# untitled.net
KiCad netlist of a schematic drawn in EAGLE
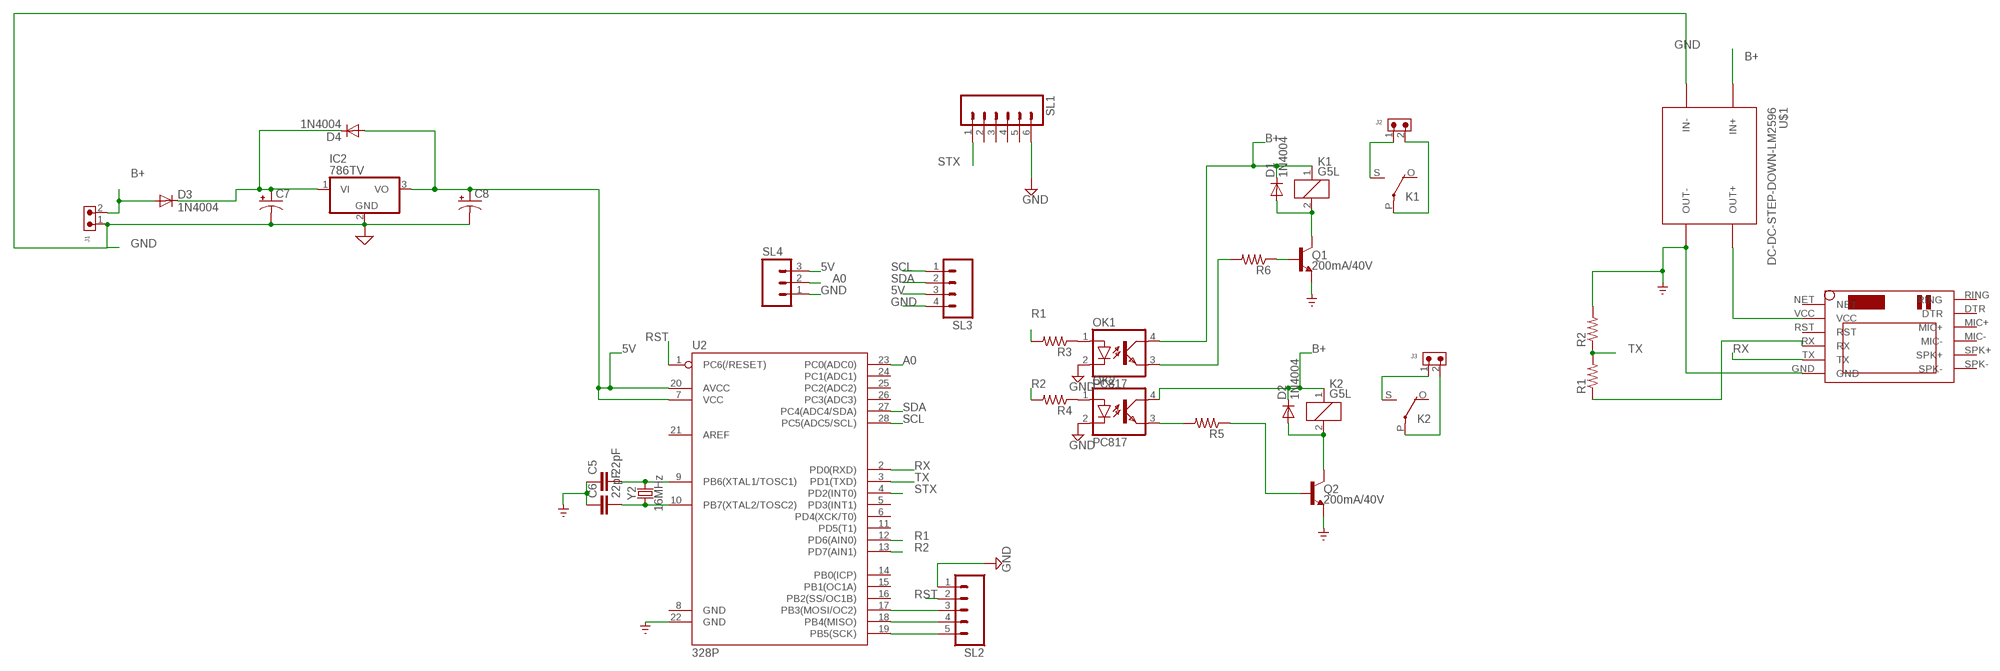
[diagram p0: schematic, sheet 1]

(export (version "E")
  (design (tool "Eeschema 10.0.6"))
  (components
    (comp (ref "C5")
      (value "22pF")
      (footprint "eagle-import:CAP-PTH-2.54")
      (libsource (lib "eagle-import") (part "22PF-PTH-2.54MM-200V-5%"))
    )
    (comp (ref "C6")
      (value "22pF")
      (footprint "eagle-import:CAP-PTH-2.54")
      (libsource (lib "eagle-import") (part "22PF-PTH-2.54MM-200V-5%"))
    )
    (comp (ref "C7")
      (value "CAPACITOR-PE5-10.5")
      (footprint "eagle-import:E5-10,5")
      (libsource (lib "eagle-import") (part "CAPACITOR-PE5-10.5"))
    )
    (comp (ref "C8")
      (value "CAPACITOR-PE5-6")
      (footprint "eagle-import:E5-6")
      (libsource (lib "eagle-import") (part "CAPACITOR-PE5-6"))
    )
    (comp (ref "D1")
      (value "1N4004")
      (footprint "eagle-import:DO41-10")
      (libsource (lib "eagle-import") (part "1N4004"))
    )
    (comp (ref "D2")
      (value "1N4004")
      (footprint "eagle-import:DO41-10")
      (libsource (lib "eagle-import") (part "1N4004"))
    )
    (comp (ref "D3")
      (value "1N4004")
      (footprint "eagle-import:DO41-10")
      (libsource (lib "eagle-import") (part "1N4004"))
    )
    (comp (ref "D4")
      (value "1N4004")
      (footprint "eagle-import:DO41-10")
      (libsource (lib "eagle-import") (part "1N4004"))
    )
    (comp (ref "IC2")
      (value "786TV")
      (footprint "eagle-import:TO220V")
      (libsource (lib "eagle-import") (part "78TV6"))
    )
    (comp (ref "J1")
      (value "691305530002")
      (footprint "eagle-import:691305530002")
      (libsource (lib "eagle-import") (part "691305530002"))
    )
    (comp (ref "J2")
      (value "691305530002")
      (footprint "eagle-import:691305530002")
      (libsource (lib "eagle-import") (part "691305530002"))
    )
    (comp (ref "J3")
      (value "691305530002")
      (footprint "eagle-import:691305530002")
      (libsource (lib "eagle-import") (part "691305530002"))
    )
    (comp (ref "K1")
      (value "G5L")
      (footprint "eagle-import:G5LE")
      (libsource (lib "eagle-import") (part "G5L"))
    )
    (comp (ref "K2")
      (value "G5L")
      (footprint "eagle-import:G5LE")
      (libsource (lib "eagle-import") (part "G5L"))
    )
    (comp (ref "OK1")
      (value "PC817")
      (footprint "eagle-import:DIL04")
      (fields (field (name "MPN") "PC817X4J000F"))
      (libsource (lib "eagle-import") (part "PC817"))
    )
    (comp (ref "OK2")
      (value "PC817")
      (footprint "eagle-import:DIL04")
      (fields (field (name "MPN") "PC817X4J000F"))
      (libsource (lib "eagle-import") (part "PC817"))
    )
    (comp (ref "Q1")
      (value "200mA/40V")
      (footprint "eagle-import:TO-92")
      (libsource (lib "eagle-import") (part "TRANS_NPN-2N3904"))
    )
    (comp (ref "Q2")
      (value "200mA/40V")
      (footprint "eagle-import:TO-92")
      (libsource (lib "eagle-import") (part "TRANS_NPN-2N3904"))
    )
    (comp (ref "R1")
      (value "R-US_0207/9")
      (footprint "eagle-import:0207_9")
      (libsource (lib "eagle-import") (part "R-US_0207/9"))
    )
    (comp (ref "R2")
      (value "R-US_0207/9")
      (footprint "eagle-import:0207_9")
      (libsource (lib "eagle-import") (part "R-US_0207/9"))
    )
    (comp (ref "R3")
      (value "R-US_0207/9")
      (footprint "eagle-import:0207_9")
      (libsource (lib "eagle-import") (part "R-US_0207/9"))
    )
    (comp (ref "R4")
      (value "R-US_0207/9")
      (footprint "eagle-import:0207_9")
      (libsource (lib "eagle-import") (part "R-US_0207/9"))
    )
    (comp (ref "R5")
      (value "R-US_0207/9")
      (footprint "eagle-import:0207_9")
      (libsource (lib "eagle-import") (part "R-US_0207/9"))
    )
    (comp (ref "R6")
      (value "R-US_0207/9")
      (footprint "eagle-import:0207_9")
      (libsource (lib "eagle-import") (part "R-US_0207/9"))
    )
    (comp (ref "SL1")
      (value "M06")
      (footprint "eagle-import:06P")
      (libsource (lib "eagle-import") (part "M06"))
    )
    (comp (ref "SL2")
      (value "M05")
      (footprint "eagle-import:05P")
      (libsource (lib "eagle-import") (part "M05"))
    )
    (comp (ref "SL3")
      (value "M04")
      (footprint "eagle-import:04P")
      (libsource (lib "eagle-import") (part "M04"))
    )
    (comp (ref "SL4")
      (value "M03")
      (footprint "eagle-import:03P")
      (libsource (lib "eagle-import") (part "M03"))
    )
    (comp (ref "U$1")
      (value "DC-DC-STEP-DOWN-LM2596")
      (footprint "eagle-import:DC-DC-STEP-DOWN-LM2596")
      (libsource (lib "eagle-import") (part "DC-DC-STEP-DOWN-LM2596"))
    )
    (comp (ref "U$2")
      (value "SIM800LMODULE")
      (footprint "eagle-import:SIM800LMODULE")
      (libsource (lib "eagle-import") (part "SIM800LMODULE"))
    )
    (comp (ref "U2")
      (value "328P")
      (footprint "eagle-import:DIP28")
      (libsource (lib "eagle-import") (part "ATMEGA328P_PDIP"))
    )
    (comp (ref "Y2")
      (value "16MHz")
      (footprint "eagle-import:HC49US")
      (libsource (lib "eagle-import") (part "CRYSTAL-16MHZPTH-HC49US"))
    )
  )
  (nets
    (net (code "1") (name "/5V") (class "Default")
      (node (ref "C8") (pin "+") (pinfunction "+_+") (pintype "passive"))
      (node (ref "D4") (pin "A") (pinfunction "A_A") (pintype "passive"))
      (node (ref "IC2") (pin "3") (pinfunction "VO_3") (pintype "passive"))
      (node (ref "SL3") (pin "3") (pinfunction "3_3") (pintype "passive"))
      (node (ref "SL4") (pin "3") (pinfunction "3_3") (pintype "passive"))
      (node (ref "U2") (pin "20") (pinfunction "AVCC_20") (pintype "bidirectional"))
      (node (ref "U2") (pin "7") (pinfunction "VCC_7") (pintype "bidirectional"))
    )
    (net (code "2") (name "/A0") (class "Default")
      (node (ref "SL4") (pin "2") (pinfunction "2_2") (pintype "passive"))
      (node (ref "U2") (pin "23") (pinfunction "PC0(ADC0)_23") (pintype "bidirectional"))
    )
    (net (code "3") (name "/B+") (class "Default")
      (node (ref "D1") (pin "C") (pinfunction "C_C") (pintype "passive"))
      (node (ref "D2") (pin "C") (pinfunction "C_C") (pintype "passive"))
      (node (ref "D3") (pin "A") (pinfunction "A_A") (pintype "passive"))
      (node (ref "J1") (pin "2") (pinfunction "2_2") (pintype "passive"))
      (node (ref "K1") (pin "1") (pinfunction "1_1") (pintype "passive"))
      (node (ref "K2") (pin "1") (pinfunction "1_1") (pintype "passive"))
      (node (ref "OK1") (pin "4") (pinfunction "COL_4") (pintype "passive"))
      (node (ref "OK2") (pin "4") (pinfunction "COL_4") (pintype "passive"))
      (node (ref "U$1") (pin "IN+") (pinfunction "IN+_IN+") (pintype "bidirectional"))
    )
    (net (code "4") (name "/R1") (class "Default")
      (node (ref "R3") (pin "2") (pinfunction "2_2") (pintype "passive"))
      (node (ref "U2") (pin "12") (pinfunction "PD6(AIN0)_12") (pintype "bidirectional"))
    )
    (net (code "5") (name "/R2") (class "Default")
      (node (ref "R4") (pin "2") (pinfunction "2_2") (pintype "passive"))
      (node (ref "U2") (pin "13") (pinfunction "PD7(AIN1)_13") (pintype "bidirectional"))
    )
    (net (code "6") (name "/RST") (class "Default")
      (node (ref "SL2") (pin "2") (pinfunction "2_2") (pintype "passive"))
      (node (ref "U2") (pin "1") (pinfunction "PC6(/RESET)_1") (pintype "bidirectional"))
    )
    (net (code "7") (name "/RX") (class "Default")
      (node (ref "U$2") (pin "TX") (pinfunction "TX_TX") (pintype "bidirectional"))
      (node (ref "U2") (pin "2") (pinfunction "PD0(RXD)_2") (pintype "bidirectional"))
    )
    (net (code "8") (name "/SCL") (class "Default")
      (node (ref "SL3") (pin "1") (pinfunction "1_1") (pintype "passive"))
      (node (ref "U2") (pin "28") (pinfunction "PC5(ADC5/SCL)_28") (pintype "bidirectional"))
    )
    (net (code "9") (name "/SDA") (class "Default")
      (node (ref "SL3") (pin "2") (pinfunction "2_2") (pintype "passive"))
      (node (ref "U2") (pin "27") (pinfunction "PC4(ADC4/SDA)_27") (pintype "bidirectional"))
    )
    (net (code "10") (name "/STX") (class "Default")
      (node (ref "SL1") (pin "1") (pinfunction "1_1") (pintype "passive"))
      (node (ref "U2") (pin "4") (pinfunction "PD2(INT0)_4") (pintype "bidirectional"))
    )
    (net (code "11") (name "/TX") (class "Default")
      (node (ref "R1") (pin "2") (pinfunction "2_2") (pintype "passive"))
      (node (ref "R2") (pin "1") (pinfunction "1_1") (pintype "passive"))
      (node (ref "U2") (pin "3") (pinfunction "PD1(TXD)_3") (pintype "bidirectional"))
    )
    (net (code "12") (name "GND") (class "Default")
      (node (ref "C5") (pin "1") (pinfunction "1_1") (pintype "passive"))
      (node (ref "C6") (pin "1") (pinfunction "1_1") (pintype "passive"))
      (node (ref "C7") (pin "-") (pinfunction "-_-") (pintype "passive"))
      (node (ref "C8") (pin "-") (pinfunction "-_-") (pintype "passive"))
      (node (ref "IC2") (pin "2") (pinfunction "GND_2") (pintype "passive"))
      (node (ref "J1") (pin "1") (pinfunction "1_1") (pintype "passive"))
      (node (ref "OK1") (pin "2") (pinfunction "C_2") (pintype "passive"))
      (node (ref "OK2") (pin "2") (pinfunction "C_2") (pintype "passive"))
      (node (ref "Q1") (pin "1") (pinfunction "E_1") (pintype "passive"))
      (node (ref "Q2") (pin "1") (pinfunction "E_1") (pintype "passive"))
      (node (ref "R2") (pin "2") (pinfunction "2_2") (pintype "passive"))
      (node (ref "SL1") (pin "6") (pinfunction "6_6") (pintype "passive"))
      (node (ref "SL2") (pin "1") (pinfunction "1_1") (pintype "passive"))
      (node (ref "SL3") (pin "4") (pinfunction "4_4") (pintype "passive"))
      (node (ref "SL4") (pin "1") (pinfunction "1_1") (pintype "passive"))
      (node (ref "U$1") (pin "IN-") (pinfunction "IN-_IN-") (pintype "bidirectional"))
      (node (ref "U$1") (pin "OUT-") (pinfunction "OUT-_OUT-") (pintype "bidirectional"))
      (node (ref "U$2") (pin "GND") (pinfunction "GND_GND") (pintype "bidirectional"))
      (node (ref "U2") (pin "22") (pinfunction "GND_22") (pintype "bidirectional"))
    )
    (net (code "13") (name "Net-(IC2-VI)") (class "Default")
      (node (ref "C7") (pin "+") (pinfunction "+_+") (pintype "passive"))
      (node (ref "D3") (pin "C") (pinfunction "C_C") (pintype "passive"))
      (node (ref "D4") (pin "C") (pinfunction "C_C") (pintype "passive"))
      (node (ref "IC2") (pin "1") (pinfunction "VI_1") (pintype "input"))
    )
    (net (code "14") (name "Net-(J2-Pad1)") (class "Default")
      (node (ref "J2") (pin "1") (pinfunction "1_1") (pintype "passive"))
      (node (ref "K1") (pin "S") (pinfunction "S_S") (pintype "passive"))
    )
    (net (code "15") (name "Net-(J2-Pad2)") (class "Default")
      (node (ref "J2") (pin "2") (pinfunction "2_2") (pintype "passive"))
      (node (ref "K1") (pin "P") (pinfunction "P_P") (pintype "passive"))
    )
    (net (code "16") (name "Net-(J3-Pad1)") (class "Default")
      (node (ref "J3") (pin "1") (pinfunction "1_1") (pintype "passive"))
      (node (ref "K2") (pin "S") (pinfunction "S_S") (pintype "passive"))
    )
    (net (code "17") (name "Net-(J3-Pad2)") (class "Default")
      (node (ref "J3") (pin "2") (pinfunction "2_2") (pintype "passive"))
      (node (ref "K2") (pin "P") (pinfunction "P_P") (pintype "passive"))
    )
    (net (code "18") (name "Net-(OK1-A)") (class "Default")
      (node (ref "OK1") (pin "1") (pinfunction "A_1") (pintype "passive"))
      (node (ref "R3") (pin "1") (pinfunction "1_1") (pintype "passive"))
    )
    (net (code "19") (name "Net-(OK1-EMIT)") (class "Default")
      (node (ref "OK1") (pin "3") (pinfunction "EMIT_3") (pintype "passive"))
      (node (ref "R6") (pin "2") (pinfunction "2_2") (pintype "passive"))
    )
    (net (code "20") (name "Net-(OK2-A)") (class "Default")
      (node (ref "OK2") (pin "1") (pinfunction "A_1") (pintype "passive"))
      (node (ref "R4") (pin "1") (pinfunction "1_1") (pintype "passive"))
    )
    (net (code "21") (name "Net-(OK2-EMIT)") (class "Default")
      (node (ref "OK2") (pin "3") (pinfunction "EMIT_3") (pintype "passive"))
      (node (ref "R5") (pin "2") (pinfunction "2_2") (pintype "passive"))
    )
    (net (code "22") (name "Net-(Q1-B)") (class "Default")
      (node (ref "Q1") (pin "2") (pinfunction "B_2") (pintype "passive"))
      (node (ref "R6") (pin "1") (pinfunction "1_1") (pintype "passive"))
    )
    (net (code "23") (name "Net-(Q1-C)") (class "Default")
      (node (ref "D1") (pin "A") (pinfunction "A_A") (pintype "passive"))
      (node (ref "K1") (pin "2") (pinfunction "2_2") (pintype "passive"))
      (node (ref "Q1") (pin "3") (pinfunction "C_3") (pintype "passive"))
    )
    (net (code "24") (name "Net-(Q2-B)") (class "Default")
      (node (ref "Q2") (pin "2") (pinfunction "B_2") (pintype "passive"))
      (node (ref "R5") (pin "1") (pinfunction "1_1") (pintype "passive"))
    )
    (net (code "25") (name "Net-(Q2-C)") (class "Default")
      (node (ref "D2") (pin "A") (pinfunction "A_A") (pintype "passive"))
      (node (ref "K2") (pin "2") (pinfunction "2_2") (pintype "passive"))
      (node (ref "Q2") (pin "3") (pinfunction "C_3") (pintype "passive"))
    )
    (net (code "26") (name "Net-(R1-Pad1)") (class "Default")
      (node (ref "R1") (pin "1") (pinfunction "1_1") (pintype "passive"))
      (node (ref "U$2") (pin "RX") (pinfunction "RX_RX") (pintype "bidirectional"))
    )
    (net (code "27") (name "Net-(U$1-PadOUT+)") (class "Default")
      (node (ref "U$1") (pin "OUT+") (pinfunction "OUT+_OUT+") (pintype "bidirectional"))
      (node (ref "U$2") (pin "VCC") (pinfunction "VCC_VCC") (pintype "bidirectional"))
    )
    (net (code "28") (name "Net-(U2-PB3(MOSI{slash}OC2))") (class "Default")
      (node (ref "SL2") (pin "3") (pinfunction "3_3") (pintype "passive"))
      (node (ref "U2") (pin "17") (pinfunction "PB3(MOSI/OC2)_17") (pintype "bidirectional"))
    )
    (net (code "29") (name "Net-(U2-PB4(MISO))") (class "Default")
      (node (ref "SL2") (pin "4") (pinfunction "4_4") (pintype "passive"))
      (node (ref "U2") (pin "18") (pinfunction "PB4(MISO)_18") (pintype "bidirectional"))
    )
    (net (code "30") (name "Net-(U2-PB5(SCK))") (class "Default")
      (node (ref "SL2") (pin "5") (pinfunction "5_5") (pintype "passive"))
      (node (ref "U2") (pin "19") (pinfunction "PB5(SCK)_19") (pintype "bidirectional"))
    )
    (net (code "31") (name "Net-(U2-PB6(XTAL1{slash}TOSC1))") (class "Default")
      (node (ref "C5") (pin "2") (pinfunction "2_2") (pintype "passive"))
      (node (ref "U2") (pin "9") (pinfunction "PB6(XTAL1/TOSC1)_9") (pintype "bidirectional"))
      (node (ref "Y2") (pin "2") (pinfunction "2_2") (pintype "passive"))
    )
    (net (code "32") (name "Net-(U2-PB7(XTAL2{slash}TOSC2))") (class "Default")
      (node (ref "C6") (pin "2") (pinfunction "2_2") (pintype "passive"))
      (node (ref "U2") (pin "10") (pinfunction "PB7(XTAL2/TOSC2)_10") (pintype "bidirectional"))
      (node (ref "Y2") (pin "1") (pinfunction "1_1") (pintype "passive"))
    )
    (net (code "33") (name "unconnected-(K1-PadO)") (class "Default")
      (node (ref "K1") (pin "O") (pinfunction "O_O") (pintype "passive"))
    )
    (net (code "34") (name "unconnected-(K2-PadO)") (class "Default")
      (node (ref "K2") (pin "O") (pinfunction "O_O") (pintype "passive"))
    )
    (net (code "35") (name "unconnected-(SL1-Pad2)") (class "Default")
      (node (ref "SL1") (pin "2") (pinfunction "2_2") (pintype "passive"))
    )
    (net (code "36") (name "unconnected-(SL1-Pad3)") (class "Default")
      (node (ref "SL1") (pin "3") (pinfunction "3_3") (pintype "passive"))
    )
    (net (code "37") (name "unconnected-(SL1-Pad4)") (class "Default")
      (node (ref "SL1") (pin "4") (pinfunction "4_4") (pintype "passive"))
    )
    (net (code "38") (name "unconnected-(SL1-Pad5)") (class "Default")
      (node (ref "SL1") (pin "5") (pinfunction "5_5") (pintype "passive"))
    )
    (net (code "39") (name "unconnected-(U$2-PadDTR)") (class "Default")
      (node (ref "U$2") (pin "DTR") (pinfunction "DTR_DTR") (pintype "bidirectional"))
    )
    (net (code "40") (name "unconnected-(U$2-PadMIC+)") (class "Default")
      (node (ref "U$2") (pin "MIC+") (pinfunction "MIC+_MIC+") (pintype "bidirectional"))
    )
    (net (code "41") (name "unconnected-(U$2-PadMIC-)") (class "Default")
      (node (ref "U$2") (pin "MIC-") (pinfunction "MIC-_MIC-") (pintype "bidirectional"))
    )
    (net (code "42") (name "unconnected-(U$2-PadNET)") (class "Default")
      (node (ref "U$2") (pin "NET") (pinfunction "NET_NET") (pintype "bidirectional"))
    )
    (net (code "43") (name "unconnected-(U$2-PadRING)") (class "Default")
      (node (ref "U$2") (pin "RING") (pinfunction "RING_RING") (pintype "bidirectional"))
    )
    (net (code "44") (name "unconnected-(U$2-PadRST)") (class "Default")
      (node (ref "U$2") (pin "RST") (pinfunction "RST_RST") (pintype "bidirectional"))
    )
    (net (code "45") (name "unconnected-(U$2-PadSPK+)") (class "Default")
      (node (ref "U$2") (pin "SPK+") (pinfunction "SPK+_SPK+") (pintype "bidirectional"))
    )
    (net (code "46") (name "unconnected-(U$2-PadSPK-)") (class "Default")
      (node (ref "U$2") (pin "SPK-") (pinfunction "SPK-_SPK-") (pintype "bidirectional"))
    )
    (net (code "47") (name "unconnected-(U2-AREF-Pad21)") (class "Default")
      (node (ref "U2") (pin "21") (pinfunction "AREF_21") (pintype "bidirectional"))
    )
    (net (code "48") (name "unconnected-(U2-GND-Pad8)") (class "Default")
      (node (ref "U2") (pin "8") (pinfunction "GND_8") (pintype "bidirectional"))
    )
    (net (code "49") (name "unconnected-(U2-PB0(ICP)-Pad14)") (class "Default")
      (node (ref "U2") (pin "14") (pinfunction "PB0(ICP)_14") (pintype "bidirectional"))
    )
    (net (code "50") (name "unconnected-(U2-PB1(OC1A)-Pad15)") (class "Default")
      (node (ref "U2") (pin "15") (pinfunction "PB1(OC1A)_15") (pintype "bidirectional"))
    )
    (net (code "51") (name "unconnected-(U2-PB2(SS{slash}OC1B)-Pad16)") (class "Default")
      (node (ref "U2") (pin "16") (pinfunction "PB2(SS/OC1B)_16") (pintype "bidirectional"))
    )
    (net (code "52") (name "unconnected-(U2-PC1(ADC1)-Pad24)") (class "Default")
      (node (ref "U2") (pin "24") (pinfunction "PC1(ADC1)_24") (pintype "bidirectional"))
    )
    (net (code "53") (name "unconnected-(U2-PC2(ADC2)-Pad25)") (class "Default")
      (node (ref "U2") (pin "25") (pinfunction "PC2(ADC2)_25") (pintype "bidirectional"))
    )
    (net (code "54") (name "unconnected-(U2-PC3(ADC3)-Pad26)") (class "Default")
      (node (ref "U2") (pin "26") (pinfunction "PC3(ADC3)_26") (pintype "bidirectional"))
    )
    (net (code "55") (name "unconnected-(U2-PD3(INT1)-Pad5)") (class "Default")
      (node (ref "U2") (pin "5") (pinfunction "PD3(INT1)_5") (pintype "bidirectional"))
    )
    (net (code "56") (name "unconnected-(U2-PD4(XCK{slash}T0)-Pad6)") (class "Default")
      (node (ref "U2") (pin "6") (pinfunction "PD4(XCK/T0)_6") (pintype "bidirectional"))
    )
    (net (code "57") (name "unconnected-(U2-PD5(T1)-Pad11)") (class "Default")
      (node (ref "U2") (pin "11") (pinfunction "PD5(T1)_11") (pintype "bidirectional"))
    )
  )
)
